# SCH_Boat_automator_2_0_2022-11-01.net
KiCad netlist of a schematic drawn in EasyEDA
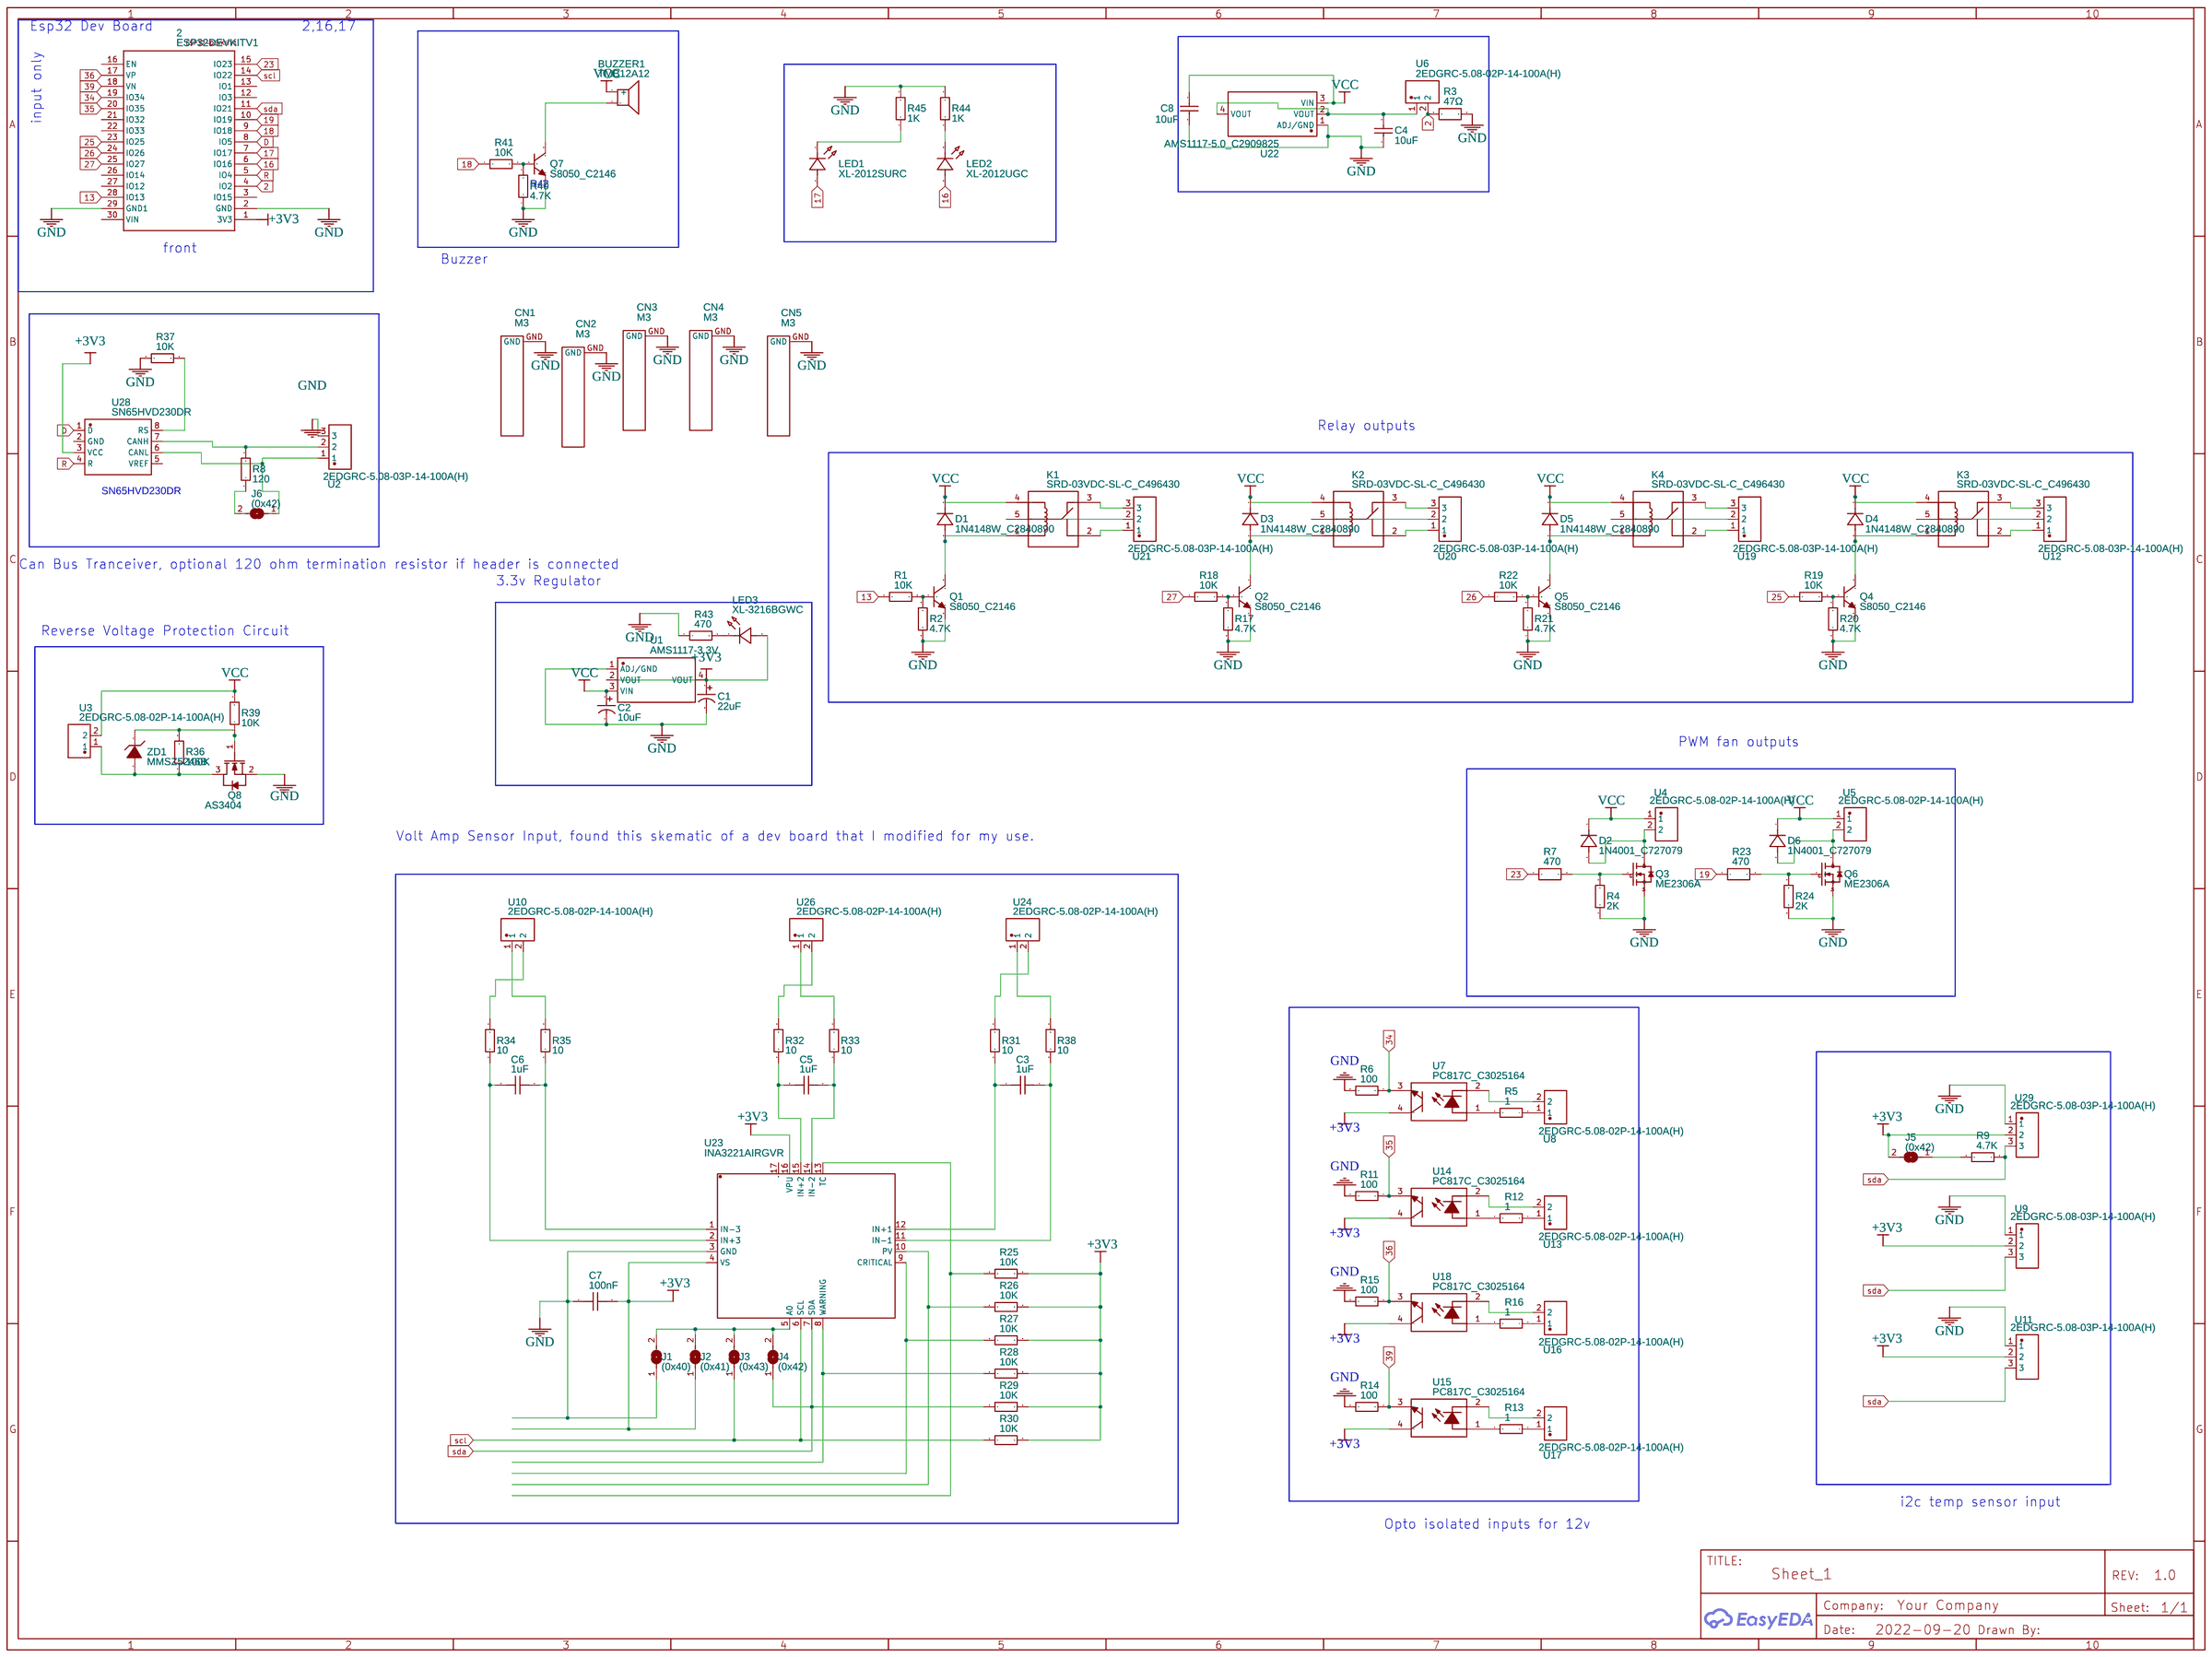
[diagram p0: schematic sheet]

(export (version "E")
  (design (tool "Eeschema 10.0.6"))
  (components
    (comp (ref "2") (value "ESP32DEVKITV1") (libsource (lib "") (part "ESP32DEVKITV1")))
    (comp (ref "BUZZER1")
      (value "TMB12A12")
      (fields (field (name "BOM_Supplier Part") "C96079"))
      (libsource (lib "") (part "TMB12A12"))
    )
    (comp (ref "C1")
      (value "22uF")
      (fields
        (field (name "BOM_Manufacturer Part") "RVT1C220M0405")
        (field (name "BOM_Supplier Part") "C72502")
      )
      (libsource (lib "") (part "RVT1C220M0405"))
    )
    (comp (ref "C2")
      (value "10uF")
      (fields
        (field (name "BOM_Manufacturer Part") "RVT1V100M0405")
        (field (name "BOM_Supplier Part") "C72485")
      )
      (libsource (lib "") (part "RVT1V100M0405-C72485"))
    )
    (comp (ref "C3")
      (value "1uF")
      (fields
        (field (name "BOM_Manufacturer Part") "CC0402KRX5R7BB105")
        (field (name "BOM_Supplier Part") "C325464")
      )
      (libsource (lib "") (part "CC0402KRX5R7BB105"))
    )
    (comp (ref "C4")
      (value "10uF")
      (fields
        (field (name "BOM_Manufacturer Part") "CC0805KKX5R8BB106")
        (field (name "BOM_Supplier Part") "C89831")
      )
      (libsource (lib "") (part "CC0805KKX5R8BB106"))
    )
    (comp (ref "C5")
      (value "1uF")
      (fields
        (field (name "BOM_Manufacturer Part") "CC0402KRX5R7BB105")
        (field (name "BOM_Supplier Part") "C325464")
      )
      (libsource (lib "") (part "CC0402KRX5R7BB105"))
    )
    (comp (ref "C6")
      (value "1uF")
      (fields
        (field (name "BOM_Manufacturer Part") "CC0402KRX5R7BB105")
        (field (name "BOM_Supplier Part") "C325464")
      )
      (libsource (lib "") (part "CC0402KRX5R7BB105"))
    )
    (comp (ref "C7")
      (value "100nF")
      (fields
        (field (name "BOM_Manufacturer Part") "CC0402KRX5R6BB104")
        (field (name "BOM_Supplier Part") "C129131")
      )
      (libsource (lib "") (part "CC0402KRX5R6BB104"))
    )
    (comp (ref "C8")
      (value "10uF")
      (fields
        (field (name "BOM_Manufacturer Part") "CC0805KKX5R8BB106")
        (field (name "BOM_Supplier Part") "C89831")
      )
      (libsource (lib "") (part "CC0805KKX5R8BB106"))
    )
    (comp (ref "CN1")
      (value "M3")
      (fields (field (name "BOM_Manufacturer Part") "XH-9A") (field (name "BOM_Supplier Part") "C8887"))
      (libsource (lib "") (part "M3"))
    )
    (comp (ref "CN2")
      (value "M3")
      (fields (field (name "BOM_Manufacturer Part") "XH-9A") (field (name "BOM_Supplier Part") "C8887"))
      (libsource (lib "") (part "M3"))
    )
    (comp (ref "CN3")
      (value "M3")
      (fields (field (name "BOM_Manufacturer Part") "XH-9A") (field (name "BOM_Supplier Part") "C8887"))
      (libsource (lib "") (part "M3"))
    )
    (comp (ref "CN4")
      (value "M3")
      (fields (field (name "BOM_Manufacturer Part") "XH-9A") (field (name "BOM_Supplier Part") "C8887"))
      (libsource (lib "") (part "M3"))
    )
    (comp (ref "CN5")
      (value "M3")
      (fields (field (name "BOM_Manufacturer Part") "XH-9A") (field (name "BOM_Supplier Part") "C8887"))
      (libsource (lib "") (part "M3"))
    )
    (comp (ref "D1")
      (value "1N4148W_C2840890")
      (fields (field (name "BOM_Manufacturer Part") "1N4148W") (field (name "BOM_Supplier Part") "C2840890"))
      (libsource (lib "") (part "1N4148W_C2840890"))
    )
    (comp (ref "D2")
      (value "1N4001_C727079")
      (fields (field (name "BOM_Manufacturer Part") "1N4001") (field (name "BOM_Supplier Part") "C727079"))
      (libsource (lib "") (part "1N4001_C727079"))
    )
    (comp (ref "D3")
      (value "1N4148W_C2840890")
      (fields (field (name "BOM_Manufacturer Part") "1N4148W") (field (name "BOM_Supplier Part") "C2840890"))
      (libsource (lib "") (part "1N4148W_C2840890"))
    )
    (comp (ref "D4")
      (value "1N4148W_C2840890")
      (fields (field (name "BOM_Manufacturer Part") "1N4148W") (field (name "BOM_Supplier Part") "C2840890"))
      (libsource (lib "") (part "1N4148W_C2840890"))
    )
    (comp (ref "D5")
      (value "1N4148W_C2840890")
      (fields (field (name "BOM_Manufacturer Part") "1N4148W") (field (name "BOM_Supplier Part") "C2840890"))
      (libsource (lib "") (part "1N4148W_C2840890"))
    )
    (comp (ref "D6")
      (value "1N4001_C727079")
      (fields (field (name "BOM_Manufacturer Part") "1N4001") (field (name "BOM_Supplier Part") "C727079"))
      (libsource (lib "") (part "1N4001_C727079"))
    )
    (comp (ref "J1")
      (value "(0x40)")
      (fields (field (name "BOM_Manufacturer Part") "?"))
      (libsource (lib "") (part "Unknown_585_400"))
    )
    (comp (ref "J2")
      (value "(0x41)")
      (fields (field (name "BOM_Manufacturer Part") "?"))
      (libsource (lib "") (part "Unknown_620_400"))
    )
    (comp (ref "J3")
      (value "(0x43)")
      (fields (field (name "BOM_Manufacturer Part") "?"))
      (libsource (lib "") (part "Unknown_655_400"))
    )
    (comp (ref "J4")
      (value "(0x42)")
      (fields (field (name "BOM_Manufacturer Part") "?"))
      (libsource (lib "") (part "Unknown_690_400"))
    )
    (comp (ref "J5")
      (value "(0x42)")
      (fields (field (name "BOM_Manufacturer Part") "?"))
      (libsource (lib "") (part "Unknown_1705_230"))
    )
    (comp (ref "J6")
      (value "(0x42)")
      (fields (field (name "BOM_Manufacturer Part") "?"))
      (libsource (lib "") (part "Unknown_215_-350"))
    )
    (comp (ref "K1")
      (value "SRD-03VDC-SL-C_C496430")
      (fields
        (field (name "BOM_Manufacturer Part") "SRD-03VDC-SL-C")
        (field (name "BOM_Supplier Part") "C496430")
      )
      (libsource (lib "") (part "SRD-03VDC-SL-C_C496430"))
    )
    (comp (ref "K2")
      (value "SRD-03VDC-SL-C_C496430")
      (fields
        (field (name "BOM_Manufacturer Part") "SRD-03VDC-SL-C")
        (field (name "BOM_Supplier Part") "C496430")
      )
      (libsource (lib "") (part "SRD-03VDC-SL-C_C496430"))
    )
    (comp (ref "K3")
      (value "SRD-03VDC-SL-C_C496430")
      (fields
        (field (name "BOM_Manufacturer Part") "SRD-03VDC-SL-C")
        (field (name "BOM_Supplier Part") "C496430")
      )
      (libsource (lib "") (part "SRD-03VDC-SL-C_C496430"))
    )
    (comp (ref "K4")
      (value "SRD-03VDC-SL-C_C496430")
      (fields
        (field (name "BOM_Manufacturer Part") "SRD-03VDC-SL-C")
        (field (name "BOM_Supplier Part") "C496430")
      )
      (libsource (lib "") (part "SRD-03VDC-SL-C_C496430"))
    )
    (comp (ref "LED1")
      (value "XL-2012SURC")
      (fields (field (name "BOM_Supplier Part") "C965812"))
      (libsource (lib "") (part "XL-2012SURC"))
    )
    (comp (ref "LED2")
      (value "XL-2012UGC")
      (fields (field (name "BOM_Supplier Part") "C965815"))
      (libsource (lib "") (part "XL-2012UGC"))
    )
    (comp (ref "LED3")
      (value "XL-3216BGWC")
      (fields (field (name "BOM_Supplier Part") "C965829"))
      (libsource (lib "") (part "XL-3216BGWC"))
    )
    (comp (ref "Q1")
      (value "S8050_C2146")
      (fields (field (name "BOM_Manufacturer Part") "S8050") (field (name "BOM_Supplier Part") "C2146"))
      (libsource (lib "") (part "S8050_C2146"))
    )
    (comp (ref "Q2")
      (value "S8050_C2146")
      (fields (field (name "BOM_Manufacturer Part") "S8050") (field (name "BOM_Supplier Part") "C2146"))
      (libsource (lib "") (part "S8050_C2146"))
    )
    (comp (ref "Q3")
      (value "ME2306A")
      (fields (field (name "BOM_Supplier Part") "C165219"))
      (libsource (lib "") (part "ME2306A"))
    )
    (comp (ref "Q4")
      (value "S8050_C2146")
      (fields (field (name "BOM_Manufacturer Part") "S8050") (field (name "BOM_Supplier Part") "C2146"))
      (libsource (lib "") (part "S8050_C2146"))
    )
    (comp (ref "Q5")
      (value "S8050_C2146")
      (fields (field (name "BOM_Manufacturer Part") "S8050") (field (name "BOM_Supplier Part") "C2146"))
      (libsource (lib "") (part "S8050_C2146"))
    )
    (comp (ref "Q6")
      (value "ME2306A")
      (fields (field (name "BOM_Supplier Part") "C165219"))
      (libsource (lib "") (part "ME2306A"))
    )
    (comp (ref "Q7")
      (value "S8050_C2146")
      (fields (field (name "BOM_Manufacturer Part") "S8050") (field (name "BOM_Supplier Part") "C2146"))
      (libsource (lib "") (part "S8050_C2146"))
    )
    (comp (ref "Q8")
      (value "AS3404")
      (fields (field (name "BOM_Supplier Part") "C232278"))
      (libsource (lib "") (part "AS3404"))
    )
    (comp (ref "R1")
      (value "10K")
      (fields
        (field (name "BOM_Manufacturer Part") "RC0603JR-0710KL")
        (field (name "BOM_Supplier Part") "C99198")
      )
      (libsource (lib "") (part "RC0603JR-0710KL"))
    )
    (comp (ref "R2")
      (value "4.7K")
      (fields
        (field (name "BOM_Manufacturer Part") "RC0603JR-074K7L")
        (field (name "BOM_Supplier Part") "C105428")
      )
      (libsource (lib "") (part "RC0603JR-074K7L"))
    )
    (comp (ref "R3")
      (value "47Ω")
      (fields
        (field (name "BOM_Manufacturer Part") "CR-12JA4---47R")
        (field (name "BOM_Supplier Part") "C881912")
      )
      (libsource (lib "") (part "CR-12JA4---47R"))
    )
    (comp (ref "R4")
      (value "2K")
      (fields
        (field (name "BOM_Manufacturer Part") "RC0603JR-072KL")
        (field (name "BOM_Supplier Part") "C105581")
      )
      (libsource (lib "") (part "RC0603JR-072KL"))
    )
    (comp (ref "R5")
      (value "1")
      (fields
        (field (name "BOM_Manufacturer Part") "RC0603FR-071RL")
        (field (name "BOM_Supplier Part") "C112305")
      )
      (libsource (lib "") (part "RC0603FR-071RL"))
    )
    (comp (ref "R6")
      (value "100")
      (fields
        (field (name "BOM_Manufacturer Part") "RC0603JR-07100RL")
        (field (name "BOM_Supplier Part") "C110091")
      )
      (libsource (lib "") (part "RC0603JR-07100RL"))
    )
    (comp (ref "R7")
      (value "470")
      (fields
        (field (name "BOM_Manufacturer Part") "AC0402FR-07470RL")
        (field (name "BOM_Supplier Part") "C227095")
      )
      (libsource (lib "") (part "AC0402FR-07470RL"))
    )
    (comp (ref "R8")
      (value "120")
      (fields
        (field (name "BOM_Manufacturer Part") "RC1206FR-07120RL")
        (field (name "BOM_Supplier Part") "C114928")
      )
      (libsource (lib "") (part "RC1206FR-07120RL"))
    )
    (comp (ref "R9")
      (value "4.7K")
      (fields
        (field (name "BOM_Manufacturer Part") "RC0603JR-074K7L")
        (field (name "BOM_Supplier Part") "C105428")
      )
      (libsource (lib "") (part "RC0603JR-074K7L_1"))
    )
    (comp (ref "R11")
      (value "100")
      (fields
        (field (name "BOM_Manufacturer Part") "RC0603JR-07100RL")
        (field (name "BOM_Supplier Part") "C110091")
      )
      (libsource (lib "") (part "RC0603JR-07100RL"))
    )
    (comp (ref "R12")
      (value "1")
      (fields
        (field (name "BOM_Manufacturer Part") "RC0603FR-071RL")
        (field (name "BOM_Supplier Part") "C112305")
      )
      (libsource (lib "") (part "RC0603FR-071RL"))
    )
    (comp (ref "R13")
      (value "1")
      (fields
        (field (name "BOM_Manufacturer Part") "RC0603FR-071RL")
        (field (name "BOM_Supplier Part") "C112305")
      )
      (libsource (lib "") (part "RC0603FR-071RL"))
    )
    (comp (ref "R14")
      (value "100")
      (fields
        (field (name "BOM_Manufacturer Part") "RC0603JR-07100RL")
        (field (name "BOM_Supplier Part") "C110091")
      )
      (libsource (lib "") (part "RC0603JR-07100RL"))
    )
    (comp (ref "R15")
      (value "100")
      (fields
        (field (name "BOM_Manufacturer Part") "RC0603JR-07100RL")
        (field (name "BOM_Supplier Part") "C110091")
      )
      (libsource (lib "") (part "RC0603JR-07100RL"))
    )
    (comp (ref "R16")
      (value "1")
      (fields
        (field (name "BOM_Manufacturer Part") "RC0603FR-071RL")
        (field (name "BOM_Supplier Part") "C112305")
      )
      (libsource (lib "") (part "RC0603FR-071RL"))
    )
    (comp (ref "R17")
      (value "4.7K")
      (fields
        (field (name "BOM_Manufacturer Part") "RC0603JR-074K7L")
        (field (name "BOM_Supplier Part") "C105428")
      )
      (libsource (lib "") (part "RC0603JR-074K7L"))
    )
    (comp (ref "R18")
      (value "10K")
      (fields
        (field (name "BOM_Manufacturer Part") "RC0603JR-0710KL")
        (field (name "BOM_Supplier Part") "C99198")
      )
      (libsource (lib "") (part "RC0603JR-0710KL"))
    )
    (comp (ref "R19")
      (value "10K")
      (fields
        (field (name "BOM_Manufacturer Part") "RC0603JR-0710KL")
        (field (name "BOM_Supplier Part") "C99198")
      )
      (libsource (lib "") (part "RC0603JR-0710KL"))
    )
    (comp (ref "R20")
      (value "4.7K")
      (fields
        (field (name "BOM_Manufacturer Part") "RC0603JR-074K7L")
        (field (name "BOM_Supplier Part") "C105428")
      )
      (libsource (lib "") (part "RC0603JR-074K7L"))
    )
    (comp (ref "R21")
      (value "4.7K")
      (fields
        (field (name "BOM_Manufacturer Part") "RC0603JR-074K7L")
        (field (name "BOM_Supplier Part") "C105428")
      )
      (libsource (lib "") (part "RC0603JR-074K7L"))
    )
    (comp (ref "R22")
      (value "10K")
      (fields
        (field (name "BOM_Manufacturer Part") "RC0603JR-0710KL")
        (field (name "BOM_Supplier Part") "C99198")
      )
      (libsource (lib "") (part "RC0603JR-0710KL"))
    )
    (comp (ref "R23")
      (value "470")
      (fields
        (field (name "BOM_Manufacturer Part") "AC0402FR-07470RL")
        (field (name "BOM_Supplier Part") "C227095")
      )
      (libsource (lib "") (part "AC0402FR-07470RL"))
    )
    (comp (ref "R24")
      (value "2K")
      (fields
        (field (name "BOM_Manufacturer Part") "RC0603JR-072KL")
        (field (name "BOM_Supplier Part") "C105581")
      )
      (libsource (lib "") (part "RC0603JR-072KL"))
    )
    (comp (ref "R25")
      (value "10K")
      (fields
        (field (name "BOM_Manufacturer Part") "RC0603JR-0710KL")
        (field (name "BOM_Supplier Part") "C99198")
      )
      (libsource (lib "") (part "RC0603JR-0710KL"))
    )
    (comp (ref "R26")
      (value "10K")
      (fields
        (field (name "BOM_Manufacturer Part") "RC0603JR-0710KL")
        (field (name "BOM_Supplier Part") "C99198")
      )
      (libsource (lib "") (part "RC0603JR-0710KL"))
    )
    (comp (ref "R27")
      (value "10K")
      (fields
        (field (name "BOM_Manufacturer Part") "RC0603JR-0710KL")
        (field (name "BOM_Supplier Part") "C99198")
      )
      (libsource (lib "") (part "RC0603JR-0710KL"))
    )
    (comp (ref "R28")
      (value "10K")
      (fields
        (field (name "BOM_Manufacturer Part") "RC0603JR-0710KL")
        (field (name "BOM_Supplier Part") "C99198")
      )
      (libsource (lib "") (part "RC0603JR-0710KL"))
    )
    (comp (ref "R29")
      (value "10K")
      (fields
        (field (name "BOM_Manufacturer Part") "RC0603JR-0710KL")
        (field (name "BOM_Supplier Part") "C99198")
      )
      (libsource (lib "") (part "RC0603JR-0710KL"))
    )
    (comp (ref "R30")
      (value "10K")
      (fields
        (field (name "BOM_Manufacturer Part") "RC0603JR-0710KL")
        (field (name "BOM_Supplier Part") "C99198")
      )
      (libsource (lib "") (part "RC0603JR-0710KL"))
    )
    (comp (ref "R31")
      (value "10")
      (fields
        (field (name "BOM_Manufacturer Part") "RC0603FR-0710RL")
        (field (name "BOM_Supplier Part") "C109318")
      )
      (libsource (lib "") (part "RC0603FR-0710RL"))
    )
    (comp (ref "R32")
      (value "10")
      (fields
        (field (name "BOM_Manufacturer Part") "RC0603FR-0710RL")
        (field (name "BOM_Supplier Part") "C109318")
      )
      (libsource (lib "") (part "RC0603FR-0710RL"))
    )
    (comp (ref "R33")
      (value "10")
      (fields
        (field (name "BOM_Manufacturer Part") "RC0603FR-0710RL")
        (field (name "BOM_Supplier Part") "C109318")
      )
      (libsource (lib "") (part "RC0603FR-0710RL"))
    )
    (comp (ref "R34")
      (value "10")
      (fields
        (field (name "BOM_Manufacturer Part") "RC0603FR-0710RL")
        (field (name "BOM_Supplier Part") "C109318")
      )
      (libsource (lib "") (part "RC0603FR-0710RL"))
    )
    (comp (ref "R35")
      (value "10")
      (fields
        (field (name "BOM_Manufacturer Part") "RC0603FR-0710RL")
        (field (name "BOM_Supplier Part") "C109318")
      )
      (libsource (lib "") (part "RC0603FR-0710RL"))
    )
    (comp (ref "R36")
      (value "100K")
      (fields
        (field (name "BOM_Manufacturer Part") "RC0603FR-07100KL")
        (field (name "BOM_Supplier Part") "C14675")
      )
      (libsource (lib "") (part "RC0603FR-07100KL"))
    )
    (comp (ref "R37")
      (value "10K")
      (fields
        (field (name "BOM_Manufacturer Part") "RC0603JR-0710KL")
        (field (name "BOM_Supplier Part") "C99198")
      )
      (libsource (lib "") (part "RC0603JR-0710KL"))
    )
    (comp (ref "R38")
      (value "10")
      (fields
        (field (name "BOM_Manufacturer Part") "RC0603FR-0710RL")
        (field (name "BOM_Supplier Part") "C109318")
      )
      (libsource (lib "") (part "RC0603FR-0710RL"))
    )
    (comp (ref "R39")
      (value "10K")
      (fields
        (field (name "BOM_Manufacturer Part") "RC0603JR-0710KL")
        (field (name "BOM_Supplier Part") "C99198")
      )
      (libsource (lib "") (part "RC0603JR-0710KL_1"))
    )
    (comp (ref "R40")
      (value "4.7K")
      (fields
        (field (name "BOM_Manufacturer Part") "RC0603JR-074K7L")
        (field (name "BOM_Supplier Part") "C105428")
      )
      (libsource (lib "") (part "RC0603JR-074K7L"))
    )
    (comp (ref "R41")
      (value "10K")
      (fields
        (field (name "BOM_Manufacturer Part") "RC0603JR-0710KL")
        (field (name "BOM_Supplier Part") "C99198")
      )
      (libsource (lib "") (part "RC0603JR-0710KL"))
    )
    (comp (ref "R43")
      (value "470")
      (fields
        (field (name "BOM_Manufacturer Part") "RC1206JR-07470RL")
        (field (name "BOM_Supplier Part") "C114948")
      )
      (libsource (lib "") (part "RC1206JR-07470RL"))
    )
    (comp (ref "R44")
      (value "1K")
      (fields
        (field (name "BOM_Manufacturer Part") "RC1206JR-071KL")
        (field (name "BOM_Supplier Part") "C112223")
      )
      (libsource (lib "") (part "RC1206JR-071KL"))
    )
    (comp (ref "R45")
      (value "1K")
      (fields
        (field (name "BOM_Manufacturer Part") "RC1206JR-071KL")
        (field (name "BOM_Supplier Part") "C112223")
      )
      (libsource (lib "") (part "RC1206JR-071KL"))
    )
    (comp (ref "U1")
      (value "AMS1117-3.3V")
      (fields (field (name "BOM_Supplier Part") "C2688239"))
      (libsource (lib "") (part "AMS1117-3.3V"))
    )
    (comp (ref "U2")
      (value "2EDGRC-5.08-03P-14-100A(H)")
      (fields (field (name "BOM_Supplier Part") "C669315"))
      (libsource (lib "") (part "2EDGRC-5.08-03P-14-100A(H)"))
    )
    (comp (ref "U3")
      (value "2EDGRC-5.08-02P-14-100A(H)")
      (fields (field (name "BOM_Supplier Part") "C669314"))
      (libsource (lib "") (part "2EDGRC-5.08-02P-14-100A(H)_3"))
    )
    (comp (ref "U4")
      (value "2EDGRC-5.08-02P-14-100A(H)")
      (fields (field (name "BOM_Supplier Part") "C669314"))
      (libsource (lib "") (part "2EDGRC-5.08-02P-14-100A(H)_2"))
    )
    (comp (ref "U5")
      (value "2EDGRC-5.08-02P-14-100A(H)")
      (fields (field (name "BOM_Supplier Part") "C669314"))
      (libsource (lib "") (part "2EDGRC-5.08-02P-14-100A(H)_2"))
    )
    (comp (ref "U6")
      (value "2EDGRC-5.08-02P-14-100A(H)")
      (fields (field (name "BOM_Supplier Part") "C669314"))
      (libsource (lib "") (part "2EDGRC-5.08-02P-14-100A(H)"))
    )
    (comp (ref "U7")
      (value "PC817C_C3025164")
      (fields (field (name "BOM_Manufacturer Part") "PC817C") (field (name "BOM_Supplier Part") "C3025164"))
      (libsource (lib "") (part "PC817C_C3025164"))
    )
    (comp (ref "U8")
      (value "2EDGRC-5.08-02P-14-100A(H)")
      (fields (field (name "BOM_Supplier Part") "C669314"))
      (libsource (lib "") (part "2EDGRC-5.08-02P-14-100A(H)_1"))
    )
    (comp (ref "U9")
      (value "2EDGRC-5.08-03P-14-100A(H)")
      (fields (field (name "BOM_Supplier Part") "C669315"))
      (libsource (lib "") (part "2EDGRC-5.08-03P-14-100A(H)_1"))
    )
    (comp (ref "U10")
      (value "2EDGRC-5.08-02P-14-100A(H)")
      (fields (field (name "BOM_Supplier Part") "C669314"))
      (libsource (lib "") (part "2EDGRC-5.08-02P-14-100A(H)"))
    )
    (comp (ref "U11")
      (value "2EDGRC-5.08-03P-14-100A(H)")
      (fields (field (name "BOM_Supplier Part") "C669315"))
      (libsource (lib "") (part "2EDGRC-5.08-03P-14-100A(H)_1"))
    )
    (comp (ref "U12")
      (value "2EDGRC-5.08-03P-14-100A(H)")
      (fields (field (name "BOM_Supplier Part") "C669315"))
      (libsource (lib "") (part "2EDGRC-5.08-03P-14-100A(H)"))
    )
    (comp (ref "U13")
      (value "2EDGRC-5.08-02P-14-100A(H)")
      (fields (field (name "BOM_Supplier Part") "C669314"))
      (libsource (lib "") (part "2EDGRC-5.08-02P-14-100A(H)_1"))
    )
    (comp (ref "U14")
      (value "PC817C_C3025164")
      (fields (field (name "BOM_Manufacturer Part") "PC817C") (field (name "BOM_Supplier Part") "C3025164"))
      (libsource (lib "") (part "PC817C_C3025164"))
    )
    (comp (ref "U15")
      (value "PC817C_C3025164")
      (fields (field (name "BOM_Manufacturer Part") "PC817C") (field (name "BOM_Supplier Part") "C3025164"))
      (libsource (lib "") (part "PC817C_C3025164"))
    )
    (comp (ref "U16")
      (value "2EDGRC-5.08-02P-14-100A(H)")
      (fields (field (name "BOM_Supplier Part") "C669314"))
      (libsource (lib "") (part "2EDGRC-5.08-02P-14-100A(H)_1"))
    )
    (comp (ref "U17")
      (value "2EDGRC-5.08-02P-14-100A(H)")
      (fields (field (name "BOM_Supplier Part") "C669314"))
      (libsource (lib "") (part "2EDGRC-5.08-02P-14-100A(H)_1"))
    )
    (comp (ref "U18")
      (value "PC817C_C3025164")
      (fields (field (name "BOM_Manufacturer Part") "PC817C") (field (name "BOM_Supplier Part") "C3025164"))
      (libsource (lib "") (part "PC817C_C3025164"))
    )
    (comp (ref "U19")
      (value "2EDGRC-5.08-03P-14-100A(H)")
      (fields (field (name "BOM_Supplier Part") "C669315"))
      (libsource (lib "") (part "2EDGRC-5.08-03P-14-100A(H)"))
    )
    (comp (ref "U20")
      (value "2EDGRC-5.08-03P-14-100A(H)")
      (fields (field (name "BOM_Supplier Part") "C669315"))
      (libsource (lib "") (part "2EDGRC-5.08-03P-14-100A(H)"))
    )
    (comp (ref "U21")
      (value "2EDGRC-5.08-03P-14-100A(H)")
      (fields (field (name "BOM_Supplier Part") "C669315"))
      (libsource (lib "") (part "2EDGRC-5.08-03P-14-100A(H)"))
    )
    (comp (ref "U22")
      (value "AMS1117-5.0_C2909825")
      (fields
        (field (name "BOM_Manufacturer Part") "AMS1117-5.0")
        (field (name "BOM_Supplier Part") "C2909825")
      )
      (libsource (lib "") (part "AMS1117-5.0_C2909825"))
    )
    (comp (ref "U23")
      (value "INA3221AIRGVR")
      (fields (field (name "BOM_Supplier Part") "C181255"))
      (libsource (lib "") (part "INA3221AIRGVR"))
    )
    (comp (ref "U24")
      (value "2EDGRC-5.08-02P-14-100A(H)")
      (fields (field (name "BOM_Supplier Part") "C669314"))
      (libsource (lib "") (part "2EDGRC-5.08-02P-14-100A(H)"))
    )
    (comp (ref "U26")
      (value "2EDGRC-5.08-02P-14-100A(H)")
      (fields (field (name "BOM_Supplier Part") "C669314"))
      (libsource (lib "") (part "2EDGRC-5.08-02P-14-100A(H)"))
    )
    (comp (ref "U28")
      (value "SN65HVD230DR")
      (fields (field (name "BOM_Supplier Part") "C12084"))
      (libsource (lib "") (part "SN65HVD230DR"))
    )
    (comp (ref "U29")
      (value "2EDGRC-5.08-03P-14-100A(H)")
      (fields (field (name "BOM_Supplier Part") "C669315"))
      (libsource (lib "") (part "2EDGRC-5.08-03P-14-100A(H)_1"))
    )
    (comp (ref "ZD1")
      (value "MMSZ5246B")
      (fields (field (name "BOM_Supplier Part") "C21544"))
      (libsource (lib "") (part "MMSZ5246B"))
    )
  )
  (nets
    (net (code "1") (name "+3V3") (class "Default")
      (node (ref "2") (pin "1") (pinfunction "3V3_1") (pintype "bidirectional"))
      (node (ref "C1") (pin "1") (pinfunction "1_1") (pintype "input"))
      (node (ref "C7") (pin "2") (pinfunction "2_2") (pintype "unspecified"))
      (node (ref "J2") (pin "1") (pinfunction "1_1") (pintype "bidirectional"))
      (node (ref "J5") (pin "2") (pinfunction "2_2") (pintype "bidirectional"))
      (node (ref "LED3") (pin "2") (pinfunction "A_2") (pintype "unspecified"))
      (node (ref "R25") (pin "2") (pinfunction "2_2") (pintype "input"))
      (node (ref "R26") (pin "2") (pinfunction "2_2") (pintype "input"))
      (node (ref "R27") (pin "2") (pinfunction "2_2") (pintype "input"))
      (node (ref "R28") (pin "2") (pinfunction "2_2") (pintype "input"))
      (node (ref "R29") (pin "2") (pinfunction "2_2") (pintype "input"))
      (node (ref "R30") (pin "2") (pinfunction "2_2") (pintype "input"))
      (node (ref "U1") (pin "2") (pinfunction "VOUT_2") (pintype "unspecified"))
      (node (ref "U1") (pin "4") (pinfunction "VOUT_4") (pintype "unspecified"))
      (node (ref "U11") (pin "2") (pinfunction "2_2") (pintype "unspecified"))
      (node (ref "U14") (pin "4") (pinfunction "4_4") (pintype "unspecified"))
      (node (ref "U15") (pin "4") (pinfunction "4_4") (pintype "unspecified"))
      (node (ref "U18") (pin "4") (pinfunction "4_4") (pintype "unspecified"))
      (node (ref "U23") (pin "16") (pinfunction "VPU_16") (pintype "unspecified"))
      (node (ref "U23") (pin "4") (pinfunction "VS_4") (pintype "unspecified"))
      (node (ref "U28") (pin "3") (pinfunction "VCC_3") (pintype "unspecified"))
      (node (ref "U29") (pin "2") (pinfunction "2_2") (pintype "unspecified"))
      (node (ref "U7") (pin "4") (pinfunction "4_4") (pintype "unspecified"))
      (node (ref "U9") (pin "2") (pinfunction "2_2") (pintype "unspecified"))
    )
    (net (code "2") (name "2") (class "Default")
      (node (ref "2") (pin "4") (pinfunction "IO2_4") (pintype "bidirectional"))
      (node (ref "R3") (pin "1") (pinfunction "1_1") (pintype "unspecified"))
      (node (ref "U6") (pin "2") (pinfunction "2_2") (pintype "unspecified"))
    )
    (net (code "3") (name "13") (class "Default")
      (node (ref "2") (pin "28") (pinfunction "IO13_28") (pintype "bidirectional"))
      (node (ref "R1") (pin "1") (pinfunction "1_1") (pintype "input"))
    )
    (net (code "4") (name "16") (class "Default")
      (node (ref "2") (pin "6") (pinfunction "IO16_6") (pintype "bidirectional"))
      (node (ref "LED2") (pin "2") (pinfunction "A_2") (pintype "unspecified"))
    )
    (net (code "5") (name "17") (class "Default")
      (node (ref "2") (pin "7") (pinfunction "IO17_7") (pintype "bidirectional"))
      (node (ref "LED1") (pin "2") (pinfunction "A_2") (pintype "unspecified"))
    )
    (net (code "6") (name "18") (class "Default")
      (node (ref "2") (pin "9") (pinfunction "IO18_9") (pintype "bidirectional"))
      (node (ref "R41") (pin "1") (pinfunction "1_1") (pintype "input"))
    )
    (net (code "7") (name "19") (class "Default")
      (node (ref "2") (pin "10") (pinfunction "IO19_10") (pintype "bidirectional"))
      (node (ref "R23") (pin "1") (pinfunction "1_1") (pintype "unspecified"))
    )
    (net (code "8") (name "23") (class "Default")
      (node (ref "2") (pin "15") (pinfunction "IO23_15") (pintype "bidirectional"))
      (node (ref "R7") (pin "1") (pinfunction "1_1") (pintype "unspecified"))
    )
    (net (code "9") (name "25") (class "Default")
      (node (ref "2") (pin "23") (pinfunction "IO25_23") (pintype "bidirectional"))
      (node (ref "R19") (pin "1") (pinfunction "1_1") (pintype "input"))
    )
    (net (code "10") (name "26") (class "Default")
      (node (ref "2") (pin "24") (pinfunction "IO26_24") (pintype "bidirectional"))
      (node (ref "R22") (pin "1") (pinfunction "1_1") (pintype "input"))
    )
    (net (code "11") (name "27") (class "Default")
      (node (ref "2") (pin "25") (pinfunction "IO27_25") (pintype "bidirectional"))
      (node (ref "R18") (pin "1") (pinfunction "1_1") (pintype "input"))
    )
    (net (code "12") (name "34") (class "Default")
      (node (ref "2") (pin "19") (pinfunction "IO34_19") (pintype "bidirectional"))
      (node (ref "R6") (pin "1") (pinfunction "1_1") (pintype "input"))
      (node (ref "U7") (pin "3") (pinfunction "3_3") (pintype "unspecified"))
    )
    (net (code "13") (name "35") (class "Default")
      (node (ref "2") (pin "20") (pinfunction "IO35_20") (pintype "bidirectional"))
      (node (ref "R11") (pin "1") (pinfunction "1_1") (pintype "input"))
      (node (ref "U14") (pin "3") (pinfunction "3_3") (pintype "unspecified"))
    )
    (net (code "14") (name "36") (class "Default")
      (node (ref "2") (pin "17") (pinfunction "VP_17") (pintype "bidirectional"))
      (node (ref "R15") (pin "1") (pinfunction "1_1") (pintype "input"))
      (node (ref "U18") (pin "3") (pinfunction "3_3") (pintype "unspecified"))
    )
    (net (code "15") (name "39") (class "Default")
      (node (ref "2") (pin "18") (pinfunction "VN_18") (pintype "bidirectional"))
      (node (ref "R14") (pin "1") (pinfunction "1_1") (pintype "input"))
      (node (ref "U15") (pin "3") (pinfunction "3_3") (pintype "unspecified"))
    )
    (net (code "16") (name "D") (class "Default")
      (node (ref "2") (pin "8") (pinfunction "IO5_8") (pintype "bidirectional"))
      (node (ref "U28") (pin "1") (pinfunction "D_1") (pintype "unspecified"))
    )
    (net (code "17") (name "GND") (class "Default")
      (node (ref "2") (pin "2") (pinfunction "GND_2") (pintype "bidirectional"))
      (node (ref "2") (pin "29") (pinfunction "GND1_29") (pintype "bidirectional"))
      (node (ref "C1") (pin "2") (pinfunction "2_2") (pintype "input"))
      (node (ref "C2") (pin "2") (pinfunction "2_2") (pintype "input"))
      (node (ref "C4") (pin "1") (pinfunction "1_1") (pintype "input"))
      (node (ref "C7") (pin "1") (pinfunction "1_1") (pintype "unspecified"))
      (node (ref "C8") (pin "1") (pinfunction "1_1") (pintype "input"))
      (node (ref "CN1") (pin "GND") (pinfunction "GND_GND") (pintype "unspecified"))
      (node (ref "CN2") (pin "GND") (pinfunction "GND_GND") (pintype "unspecified"))
      (node (ref "CN3") (pin "GND") (pinfunction "GND_GND") (pintype "unspecified"))
      (node (ref "CN4") (pin "GND") (pinfunction "GND_GND") (pintype "unspecified"))
      (node (ref "CN5") (pin "GND") (pinfunction "GND_GND") (pintype "unspecified"))
      (node (ref "J1") (pin "1") (pinfunction "1_1") (pintype "bidirectional"))
      (node (ref "Q1") (pin "2") (pinfunction "E_2") (pintype "unspecified"))
      (node (ref "Q2") (pin "2") (pinfunction "E_2") (pintype "unspecified"))
      (node (ref "Q3") (pin "2") (pinfunction "S_2") (pintype "unspecified"))
      (node (ref "Q4") (pin "2") (pinfunction "E_2") (pintype "unspecified"))
      (node (ref "Q5") (pin "2") (pinfunction "E_2") (pintype "unspecified"))
      (node (ref "Q6") (pin "2") (pinfunction "S_2") (pintype "unspecified"))
      (node (ref "Q7") (pin "2") (pinfunction "E_2") (pintype "unspecified"))
      (node (ref "Q8") (pin "2") (pinfunction "S_2") (pintype "unspecified"))
      (node (ref "R11") (pin "2") (pinfunction "2_2") (pintype "input"))
      (node (ref "R14") (pin "2") (pinfunction "2_2") (pintype "input"))
      (node (ref "R15") (pin "2") (pinfunction "2_2") (pintype "input"))
      (node (ref "R17") (pin "1") (pinfunction "1_1") (pintype "input"))
      (node (ref "R2") (pin "1") (pinfunction "1_1") (pintype "input"))
      (node (ref "R20") (pin "1") (pinfunction "1_1") (pintype "input"))
      (node (ref "R21") (pin "1") (pinfunction "1_1") (pintype "input"))
      (node (ref "R24") (pin "1") (pinfunction "1_1") (pintype "input"))
      (node (ref "R3") (pin "2") (pinfunction "2_2") (pintype "unspecified"))
      (node (ref "R37") (pin "1") (pinfunction "1_1") (pintype "input"))
      (node (ref "R4") (pin "1") (pinfunction "1_1") (pintype "input"))
      (node (ref "R40") (pin "1") (pinfunction "1_1") (pintype "input"))
      (node (ref "R43") (pin "1") (pinfunction "1_1") (pintype "input"))
      (node (ref "R44") (pin "2") (pinfunction "2_2") (pintype "input"))
      (node (ref "R45") (pin "2") (pinfunction "2_2") (pintype "input"))
      (node (ref "R6") (pin "2") (pinfunction "2_2") (pintype "input"))
      (node (ref "U1") (pin "1") (pinfunction "ADJ/GND_1") (pintype "unspecified"))
      (node (ref "U11") (pin "1") (pinfunction "1_1") (pintype "unspecified"))
      (node (ref "U2") (pin "3") (pinfunction "3_3") (pintype "unspecified"))
      (node (ref "U22") (pin "1") (pinfunction "ADJ/GND_1") (pintype "unspecified"))
      (node (ref "U23") (pin "3") (pinfunction "GND_3") (pintype "unspecified"))
      (node (ref "U29") (pin "1") (pinfunction "1_1") (pintype "unspecified"))
      (node (ref "U9") (pin "1") (pinfunction "1_1") (pintype "unspecified"))
    )
    (net (code "18") (name "Net-(C4-Pad2)") (class "Default")
      (node (ref "C4") (pin "2") (pinfunction "2_2") (pintype "input"))
      (node (ref "U22") (pin "2") (pinfunction "VOUT_2") (pintype "unspecified"))
      (node (ref "U22") (pin "4") (pinfunction "VOUT_4") (pintype "unspecified"))
      (node (ref "U6") (pin "1") (pinfunction "1_1") (pintype "unspecified"))
    )
    (net (code "19") (name "Net-(D1-A)") (class "Default")
      (node (ref "D1") (pin "2") (pinfunction "A_2") (pintype "unspecified"))
      (node (ref "K1") (pin "1") (pinfunction "1_1") (pintype "unspecified"))
      (node (ref "Q1") (pin "3") (pinfunction "C_3") (pintype "unspecified"))
    )
    (net (code "20") (name "Net-(D2-A)") (class "Default")
      (node (ref "D2") (pin "2") (pinfunction "A_2") (pintype "unspecified"))
      (node (ref "Q3") (pin "3") (pinfunction "D_3") (pintype "unspecified"))
      (node (ref "U4") (pin "2") (pinfunction "2_2") (pintype "unspecified"))
    )
    (net (code "21") (name "Net-(D3-A)") (class "Default")
      (node (ref "D3") (pin "2") (pinfunction "A_2") (pintype "unspecified"))
      (node (ref "K2") (pin "1") (pinfunction "1_1") (pintype "unspecified"))
      (node (ref "Q2") (pin "3") (pinfunction "C_3") (pintype "unspecified"))
    )
    (net (code "22") (name "Net-(D4-A)") (class "Default")
      (node (ref "D4") (pin "2") (pinfunction "A_2") (pintype "unspecified"))
      (node (ref "K3") (pin "1") (pinfunction "1_1") (pintype "unspecified"))
      (node (ref "Q4") (pin "3") (pinfunction "C_3") (pintype "unspecified"))
    )
    (net (code "23") (name "Net-(D5-A)") (class "Default")
      (node (ref "D5") (pin "2") (pinfunction "A_2") (pintype "unspecified"))
      (node (ref "K4") (pin "1") (pinfunction "1_1") (pintype "unspecified"))
      (node (ref "Q5") (pin "3") (pinfunction "C_3") (pintype "unspecified"))
    )
    (net (code "24") (name "Net-(D6-A)") (class "Default")
      (node (ref "D6") (pin "2") (pinfunction "A_2") (pintype "unspecified"))
      (node (ref "Q6") (pin "3") (pinfunction "D_3") (pintype "unspecified"))
      (node (ref "U5") (pin "2") (pinfunction "2_2") (pintype "unspecified"))
    )
    (net (code "25") (name "Net-(J5-Pad1)") (class "Default")
      (node (ref "J5") (pin "1") (pinfunction "1_1") (pintype "bidirectional"))
      (node (ref "R9") (pin "2") (pinfunction "2_2") (pintype "input"))
    )
    (net (code "26") (name "Net-(J6-Pad2)") (class "Default")
      (node (ref "J6") (pin "2") (pinfunction "2_2") (pintype "bidirectional"))
      (node (ref "R8") (pin "1") (pinfunction "1_1") (pintype "input"))
    )
    (net (code "27") (name "Net-(K1-Pad2)") (class "Default")
      (node (ref "K1") (pin "2") (pinfunction "2_2") (pintype "unspecified"))
      (node (ref "U21") (pin "1") (pinfunction "1_1") (pintype "unspecified"))
    )
    (net (code "28") (name "Net-(K1-Pad3)") (class "Default")
      (node (ref "K1") (pin "3") (pinfunction "3_3") (pintype "unspecified"))
      (node (ref "U21") (pin "3") (pinfunction "3_3") (pintype "unspecified"))
    )
    (net (code "29") (name "Net-(K1-Pad5)") (class "Default")
      (node (ref "K1") (pin "5") (pinfunction "5_5") (pintype "unspecified"))
      (node (ref "U21") (pin "2") (pinfunction "2_2") (pintype "unspecified"))
    )
    (net (code "30") (name "Net-(K2-Pad2)") (class "Default")
      (node (ref "K2") (pin "2") (pinfunction "2_2") (pintype "unspecified"))
      (node (ref "U20") (pin "1") (pinfunction "1_1") (pintype "unspecified"))
    )
    (net (code "31") (name "Net-(K2-Pad3)") (class "Default")
      (node (ref "K2") (pin "3") (pinfunction "3_3") (pintype "unspecified"))
      (node (ref "U20") (pin "3") (pinfunction "3_3") (pintype "unspecified"))
    )
    (net (code "32") (name "Net-(K2-Pad5)") (class "Default")
      (node (ref "K2") (pin "5") (pinfunction "5_5") (pintype "unspecified"))
      (node (ref "U20") (pin "2") (pinfunction "2_2") (pintype "unspecified"))
    )
    (net (code "33") (name "Net-(K3-Pad2)") (class "Default")
      (node (ref "K3") (pin "2") (pinfunction "2_2") (pintype "unspecified"))
      (node (ref "U12") (pin "1") (pinfunction "1_1") (pintype "unspecified"))
    )
    (net (code "34") (name "Net-(K3-Pad3)") (class "Default")
      (node (ref "K3") (pin "3") (pinfunction "3_3") (pintype "unspecified"))
      (node (ref "U12") (pin "3") (pinfunction "3_3") (pintype "unspecified"))
    )
    (net (code "35") (name "Net-(K3-Pad5)") (class "Default")
      (node (ref "K3") (pin "5") (pinfunction "5_5") (pintype "unspecified"))
      (node (ref "U12") (pin "2") (pinfunction "2_2") (pintype "unspecified"))
    )
    (net (code "36") (name "Net-(K4-Pad2)") (class "Default")
      (node (ref "K4") (pin "2") (pinfunction "2_2") (pintype "unspecified"))
      (node (ref "U19") (pin "1") (pinfunction "1_1") (pintype "unspecified"))
    )
    (net (code "37") (name "Net-(K4-Pad3)") (class "Default")
      (node (ref "K4") (pin "3") (pinfunction "3_3") (pintype "unspecified"))
      (node (ref "U19") (pin "3") (pinfunction "3_3") (pintype "unspecified"))
    )
    (net (code "38") (name "Net-(K4-Pad5)") (class "Default")
      (node (ref "K4") (pin "5") (pinfunction "5_5") (pintype "unspecified"))
      (node (ref "U19") (pin "2") (pinfunction "2_2") (pintype "unspecified"))
    )
    (net (code "39") (name "Net-(LED1-K)") (class "Default")
      (node (ref "LED1") (pin "1") (pinfunction "K_1") (pintype "unspecified"))
      (node (ref "R45") (pin "1") (pinfunction "1_1") (pintype "input"))
    )
    (net (code "40") (name "Net-(LED2-K)") (class "Default")
      (node (ref "LED2") (pin "1") (pinfunction "K_1") (pintype "unspecified"))
      (node (ref "R44") (pin "1") (pinfunction "1_1") (pintype "input"))
    )
    (net (code "41") (name "Net-(LED3-K)") (class "Default")
      (node (ref "LED3") (pin "1") (pinfunction "K_1") (pintype "unspecified"))
      (node (ref "R43") (pin "2") (pinfunction "2_2") (pintype "input"))
    )
    (net (code "42") (name "Net-(Q1-B)") (class "Default")
      (node (ref "Q1") (pin "1") (pinfunction "B_1") (pintype "unspecified"))
      (node (ref "R1") (pin "2") (pinfunction "2_2") (pintype "input"))
      (node (ref "R2") (pin "2") (pinfunction "2_2") (pintype "input"))
    )
    (net (code "43") (name "Net-(Q2-B)") (class "Default")
      (node (ref "Q2") (pin "1") (pinfunction "B_1") (pintype "unspecified"))
      (node (ref "R17") (pin "2") (pinfunction "2_2") (pintype "input"))
      (node (ref "R18") (pin "2") (pinfunction "2_2") (pintype "input"))
    )
    (net (code "44") (name "Net-(Q3-G)") (class "Default")
      (node (ref "Q3") (pin "1") (pinfunction "G_1") (pintype "unspecified"))
      (node (ref "R4") (pin "2") (pinfunction "2_2") (pintype "input"))
      (node (ref "R7") (pin "2") (pinfunction "2_2") (pintype "unspecified"))
    )
    (net (code "45") (name "Net-(Q4-B)") (class "Default")
      (node (ref "Q4") (pin "1") (pinfunction "B_1") (pintype "unspecified"))
      (node (ref "R19") (pin "2") (pinfunction "2_2") (pintype "input"))
      (node (ref "R20") (pin "2") (pinfunction "2_2") (pintype "input"))
    )
    (net (code "46") (name "Net-(Q5-B)") (class "Default")
      (node (ref "Q5") (pin "1") (pinfunction "B_1") (pintype "unspecified"))
      (node (ref "R21") (pin "2") (pinfunction "2_2") (pintype "input"))
      (node (ref "R22") (pin "2") (pinfunction "2_2") (pintype "input"))
    )
    (net (code "47") (name "Net-(Q6-G)") (class "Default")
      (node (ref "Q6") (pin "1") (pinfunction "G_1") (pintype "unspecified"))
      (node (ref "R23") (pin "2") (pinfunction "2_2") (pintype "unspecified"))
      (node (ref "R24") (pin "2") (pinfunction "2_2") (pintype "input"))
    )
    (net (code "48") (name "Net-(Q7-B)") (class "Default")
      (node (ref "Q7") (pin "1") (pinfunction "B_1") (pintype "unspecified"))
      (node (ref "R40") (pin "2") (pinfunction "2_2") (pintype "input"))
      (node (ref "R41") (pin "2") (pinfunction "2_2") (pintype "input"))
    )
    (net (code "49") (name "Net-(Q7-C)") (class "Default")
      (node (ref "BUZZER1") (pin "2") (pinfunction "2_2") (pintype "unspecified"))
      (node (ref "Q7") (pin "3") (pinfunction "C_3") (pintype "unspecified"))
    )
    (net (code "50") (name "Net-(Q8-D)") (class "Default")
      (node (ref "Q8") (pin "3") (pinfunction "D_3") (pintype "unspecified"))
      (node (ref "R36") (pin "1") (pinfunction "1_1") (pintype "unspecified"))
      (node (ref "U3") (pin "1") (pinfunction "1_1") (pintype "unspecified"))
      (node (ref "ZD1") (pin "2") (pinfunction "A_2") (pintype "unspecified"))
    )
    (net (code "51") (name "Net-(Q8-G)") (class "Default")
      (node (ref "Q8") (pin "1") (pinfunction "G_1") (pintype "unspecified"))
      (node (ref "R36") (pin "2") (pinfunction "2_2") (pintype "unspecified"))
      (node (ref "R39") (pin "1") (pinfunction "1_1") (pintype "input"))
      (node (ref "ZD1") (pin "1") (pinfunction "K_1") (pintype "unspecified"))
    )
    (net (code "52") (name "Net-(R5-Pad1)") (class "Default")
      (node (ref "R5") (pin "1") (pinfunction "1_1") (pintype "input"))
      (node (ref "U8") (pin "1") (pinfunction "1_1") (pintype "unspecified"))
    )
    (net (code "53") (name "Net-(R5-Pad2)") (class "Default")
      (node (ref "R5") (pin "2") (pinfunction "2_2") (pintype "input"))
      (node (ref "U7") (pin "1") (pinfunction "1_1") (pintype "unspecified"))
    )
    (net (code "54") (name "Net-(R12-Pad1)") (class "Default")
      (node (ref "R12") (pin "1") (pinfunction "1_1") (pintype "input"))
      (node (ref "U13") (pin "1") (pinfunction "1_1") (pintype "unspecified"))
    )
    (net (code "55") (name "Net-(R12-Pad2)") (class "Default")
      (node (ref "R12") (pin "2") (pinfunction "2_2") (pintype "input"))
      (node (ref "U14") (pin "1") (pinfunction "1_1") (pintype "unspecified"))
    )
    (net (code "56") (name "Net-(R13-Pad1)") (class "Default")
      (node (ref "R13") (pin "1") (pinfunction "1_1") (pintype "input"))
      (node (ref "U17") (pin "1") (pinfunction "1_1") (pintype "unspecified"))
    )
    (net (code "57") (name "Net-(R13-Pad2)") (class "Default")
      (node (ref "R13") (pin "2") (pinfunction "2_2") (pintype "input"))
      (node (ref "U15") (pin "1") (pinfunction "1_1") (pintype "unspecified"))
    )
    (net (code "58") (name "Net-(R16-Pad1)") (class "Default")
      (node (ref "R16") (pin "1") (pinfunction "1_1") (pintype "input"))
      (node (ref "U16") (pin "1") (pinfunction "1_1") (pintype "unspecified"))
    )
    (net (code "59") (name "Net-(R16-Pad2)") (class "Default")
      (node (ref "R16") (pin "2") (pinfunction "2_2") (pintype "input"))
      (node (ref "U18") (pin "1") (pinfunction "1_1") (pintype "unspecified"))
    )
    (net (code "60") (name "Net-(R31-Pad2)") (class "Default")
      (node (ref "R31") (pin "2") (pinfunction "2_2") (pintype "input"))
      (node (ref "U24") (pin "2") (pinfunction "2_2") (pintype "unspecified"))
    )
    (net (code "61") (name "Net-(R32-Pad2)") (class "Default")
      (node (ref "R32") (pin "2") (pinfunction "2_2") (pintype "input"))
      (node (ref "U26") (pin "2") (pinfunction "2_2") (pintype "unspecified"))
    )
    (net (code "62") (name "Net-(R33-Pad2)") (class "Default")
      (node (ref "R33") (pin "2") (pinfunction "2_2") (pintype "input"))
      (node (ref "U26") (pin "1") (pinfunction "1_1") (pintype "unspecified"))
    )
    (net (code "63") (name "Net-(R34-Pad2)") (class "Default")
      (node (ref "R34") (pin "2") (pinfunction "2_2") (pintype "input"))
      (node (ref "U10") (pin "2") (pinfunction "2_2") (pintype "unspecified"))
    )
    (net (code "64") (name "Net-(R35-Pad2)") (class "Default")
      (node (ref "R35") (pin "2") (pinfunction "2_2") (pintype "input"))
      (node (ref "U10") (pin "1") (pinfunction "1_1") (pintype "unspecified"))
    )
    (net (code "65") (name "Net-(R38-Pad2)") (class "Default")
      (node (ref "R38") (pin "2") (pinfunction "2_2") (pintype "input"))
      (node (ref "U24") (pin "1") (pinfunction "1_1") (pintype "unspecified"))
    )
    (net (code "66") (name "Net-(U7-Pad2)") (class "Default")
      (node (ref "U7") (pin "2") (pinfunction "2_2") (pintype "unspecified"))
      (node (ref "U8") (pin "2") (pinfunction "2_2") (pintype "unspecified"))
    )
    (net (code "67") (name "Net-(U13-Pad2)") (class "Default")
      (node (ref "U13") (pin "2") (pinfunction "2_2") (pintype "unspecified"))
      (node (ref "U14") (pin "2") (pinfunction "2_2") (pintype "unspecified"))
    )
    (net (code "68") (name "Net-(U15-Pad2)") (class "Default")
      (node (ref "U15") (pin "2") (pinfunction "2_2") (pintype "unspecified"))
      (node (ref "U17") (pin "2") (pinfunction "2_2") (pintype "unspecified"))
    )
    (net (code "69") (name "Net-(U16-Pad2)") (class "Default")
      (node (ref "U16") (pin "2") (pinfunction "2_2") (pintype "unspecified"))
      (node (ref "U18") (pin "2") (pinfunction "2_2") (pintype "unspecified"))
    )
    (net (code "70") (name "Net-(U23-A0)") (class "Default")
      (node (ref "J1") (pin "2") (pinfunction "2_2") (pintype "bidirectional"))
      (node (ref "J2") (pin "2") (pinfunction "2_2") (pintype "bidirectional"))
      (node (ref "J3") (pin "2") (pinfunction "2_2") (pintype "bidirectional"))
      (node (ref "J4") (pin "2") (pinfunction "2_2") (pintype "bidirectional"))
      (node (ref "U23") (pin "5") (pinfunction "A0_5") (pintype "unspecified"))
    )
    (net (code "71") (name "Net-(U23-CRITICAL)") (class "Default")
      (node (ref "R27") (pin "1") (pinfunction "1_1") (pintype "input"))
      (node (ref "U23") (pin "9") (pinfunction "CRITICAL_9") (pintype "unspecified"))
    )
    (net (code "72") (name "Net-(U23-IN+1)") (class "Default")
      (node (ref "C3") (pin "2") (pinfunction "2_2") (pintype "unspecified"))
      (node (ref "R31") (pin "1") (pinfunction "1_1") (pintype "input"))
      (node (ref "U23") (pin "12") (pinfunction "IN+1_12") (pintype "unspecified"))
    )
    (net (code "73") (name "Net-(U23-IN+2)") (class "Default")
      (node (ref "C5") (pin "2") (pinfunction "2_2") (pintype "unspecified"))
      (node (ref "R32") (pin "1") (pinfunction "1_1") (pintype "input"))
      (node (ref "U23") (pin "15") (pinfunction "IN+2_15") (pintype "unspecified"))
    )
    (net (code "74") (name "Net-(U23-IN+3)") (class "Default")
      (node (ref "C6") (pin "2") (pinfunction "2_2") (pintype "unspecified"))
      (node (ref "R34") (pin "1") (pinfunction "1_1") (pintype "input"))
      (node (ref "U23") (pin "2") (pinfunction "IN+3_2") (pintype "unspecified"))
    )
    (net (code "75") (name "Net-(U23-IN-1)") (class "Default")
      (node (ref "C3") (pin "1") (pinfunction "1_1") (pintype "unspecified"))
      (node (ref "R38") (pin "1") (pinfunction "1_1") (pintype "input"))
      (node (ref "U23") (pin "11") (pinfunction "IN-1_11") (pintype "unspecified"))
    )
    (net (code "76") (name "Net-(U23-IN-2)") (class "Default")
      (node (ref "C5") (pin "1") (pinfunction "1_1") (pintype "unspecified"))
      (node (ref "R33") (pin "1") (pinfunction "1_1") (pintype "input"))
      (node (ref "U23") (pin "14") (pinfunction "IN-2_14") (pintype "unspecified"))
    )
    (net (code "77") (name "Net-(U23-IN-3)") (class "Default")
      (node (ref "C6") (pin "1") (pinfunction "1_1") (pintype "unspecified"))
      (node (ref "R35") (pin "1") (pinfunction "1_1") (pintype "input"))
      (node (ref "U23") (pin "1") (pinfunction "IN-3_1") (pintype "unspecified"))
    )
    (net (code "78") (name "Net-(U23-PV)") (class "Default")
      (node (ref "R26") (pin "1") (pinfunction "1_1") (pintype "input"))
      (node (ref "U23") (pin "10") (pinfunction "PV_10") (pintype "unspecified"))
    )
    (net (code "79") (name "Net-(U23-TC)") (class "Default")
      (node (ref "R25") (pin "1") (pinfunction "1_1") (pintype "input"))
      (node (ref "U23") (pin "13") (pinfunction "TC_13") (pintype "unspecified"))
    )
    (net (code "80") (name "Net-(U23-WARNING)") (class "Default")
      (node (ref "R28") (pin "1") (pinfunction "1_1") (pintype "input"))
      (node (ref "U23") (pin "8") (pinfunction "WARNING_8") (pintype "unspecified"))
    )
    (net (code "81") (name "Net-(U28-CANH)") (class "Default")
      (node (ref "R8") (pin "2") (pinfunction "2_2") (pintype "input"))
      (node (ref "U2") (pin "2") (pinfunction "2_2") (pintype "unspecified"))
      (node (ref "U28") (pin "7") (pinfunction "CANH_7") (pintype "unspecified"))
    )
    (net (code "82") (name "Net-(U28-CANL)") (class "Default")
      (node (ref "J6") (pin "1") (pinfunction "1_1") (pintype "bidirectional"))
      (node (ref "U2") (pin "1") (pinfunction "1_1") (pintype "unspecified"))
      (node (ref "U28") (pin "6") (pinfunction "CANL_6") (pintype "unspecified"))
    )
    (net (code "83") (name "Net-(U28-RS)") (class "Default")
      (node (ref "R37") (pin "2") (pinfunction "2_2") (pintype "input"))
      (node (ref "U28") (pin "8") (pinfunction "RS_8") (pintype "unspecified"))
    )
    (net (code "84") (name "R") (class "Default")
      (node (ref "2") (pin "5") (pinfunction "IO4_5") (pintype "bidirectional"))
      (node (ref "U28") (pin "4") (pinfunction "R_4") (pintype "unspecified"))
    )
    (net (code "85") (name "VCC") (class "Default")
      (node (ref "BUZZER1") (pin "1") (pinfunction "+_1") (pintype "unspecified"))
      (node (ref "C2") (pin "1") (pinfunction "1_1") (pintype "input"))
      (node (ref "C8") (pin "2") (pinfunction "2_2") (pintype "input"))
      (node (ref "D1") (pin "1") (pinfunction "K_1") (pintype "unspecified"))
      (node (ref "D2") (pin "1") (pinfunction "K_1") (pintype "unspecified"))
      (node (ref "D3") (pin "1") (pinfunction "K_1") (pintype "unspecified"))
      (node (ref "D4") (pin "1") (pinfunction "K_1") (pintype "unspecified"))
      (node (ref "D5") (pin "1") (pinfunction "K_1") (pintype "unspecified"))
      (node (ref "D6") (pin "1") (pinfunction "K_1") (pintype "unspecified"))
      (node (ref "K1") (pin "4") (pinfunction "4_4") (pintype "unspecified"))
      (node (ref "K2") (pin "4") (pinfunction "4_4") (pintype "unspecified"))
      (node (ref "K3") (pin "4") (pinfunction "4_4") (pintype "unspecified"))
      (node (ref "K4") (pin "4") (pinfunction "4_4") (pintype "unspecified"))
      (node (ref "R39") (pin "2") (pinfunction "2_2") (pintype "input"))
      (node (ref "U1") (pin "3") (pinfunction "VIN_3") (pintype "unspecified"))
      (node (ref "U22") (pin "3") (pinfunction "VIN_3") (pintype "unspecified"))
      (node (ref "U3") (pin "2") (pinfunction "2_2") (pintype "unspecified"))
      (node (ref "U4") (pin "1") (pinfunction "1_1") (pintype "unspecified"))
      (node (ref "U5") (pin "1") (pinfunction "1_1") (pintype "unspecified"))
    )
    (net (code "86") (name "scl") (class "Default")
      (node (ref "2") (pin "14") (pinfunction "IO22_14") (pintype "bidirectional"))
      (node (ref "J3") (pin "1") (pinfunction "1_1") (pintype "bidirectional"))
      (node (ref "R30") (pin "1") (pinfunction "1_1") (pintype "input"))
      (node (ref "U23") (pin "6") (pinfunction "SCL_6") (pintype "unspecified"))
    )
    (net (code "87") (name "sda") (class "Default")
      (node (ref "2") (pin "11") (pinfunction "IO21_11") (pintype "bidirectional"))
      (node (ref "J4") (pin "1") (pinfunction "1_1") (pintype "bidirectional"))
      (node (ref "R29") (pin "1") (pinfunction "1_1") (pintype "input"))
      (node (ref "R9") (pin "1") (pinfunction "1_1") (pintype "input"))
      (node (ref "U11") (pin "3") (pinfunction "3_3") (pintype "unspecified"))
      (node (ref "U23") (pin "7") (pinfunction "SDA_7") (pintype "unspecified"))
      (node (ref "U29") (pin "3") (pinfunction "3_3") (pintype "unspecified"))
      (node (ref "U9") (pin "3") (pinfunction "3_3") (pintype "unspecified"))
    )
    (net (code "88") (name "unconnected-(2-EN-Pad16)") (class "Default")
      (node (ref "2") (pin "16") (pinfunction "EN_16") (pintype "bidirectional"))
    )
    (net (code "89") (name "unconnected-(2-IO1-Pad13)") (class "Default")
      (node (ref "2") (pin "13") (pinfunction "IO1_13") (pintype "bidirectional"))
    )
    (net (code "90") (name "unconnected-(2-IO3-Pad12)") (class "Default")
      (node (ref "2") (pin "12") (pinfunction "IO3_12") (pintype "bidirectional"))
    )
    (net (code "91") (name "unconnected-(2-IO12-Pad27)") (class "Default")
      (node (ref "2") (pin "27") (pinfunction "IO12_27") (pintype "bidirectional"))
    )
    (net (code "92") (name "unconnected-(2-IO14-Pad26)") (class "Default")
      (node (ref "2") (pin "26") (pinfunction "IO14_26") (pintype "bidirectional"))
    )
    (net (code "93") (name "unconnected-(2-IO15-Pad3)") (class "Default")
      (node (ref "2") (pin "3") (pinfunction "IO15_3") (pintype "bidirectional"))
    )
    (net (code "94") (name "unconnected-(2-IO32-Pad21)") (class "Default")
      (node (ref "2") (pin "21") (pinfunction "IO32_21") (pintype "bidirectional"))
    )
    (net (code "95") (name "unconnected-(2-IO33-Pad22)") (class "Default")
      (node (ref "2") (pin "22") (pinfunction "IO33_22") (pintype "bidirectional"))
    )
    (net (code "96") (name "unconnected-(2-VIN-Pad30)") (class "Default")
      (node (ref "2") (pin "30") (pinfunction "VIN_30") (pintype "bidirectional"))
    )
    (net (code "97") (name "unconnected-(U23-PAD-Pad17)") (class "Default")
      (node (ref "U23") (pin "17") (pinfunction "PAD_17") (pintype "unspecified"))
    )
    (net (code "98") (name "unconnected-(U28-GND-Pad2)") (class "Default")
      (node (ref "U28") (pin "2") (pinfunction "GND_2") (pintype "unspecified"))
    )
    (net (code "99") (name "unconnected-(U28-VREF-Pad5)") (class "Default")
      (node (ref "U28") (pin "5") (pinfunction "VREF_5") (pintype "unspecified"))
    )
  )
)
